# MCU.net
KiCad netlist of a schematic drawn in Altium Designer
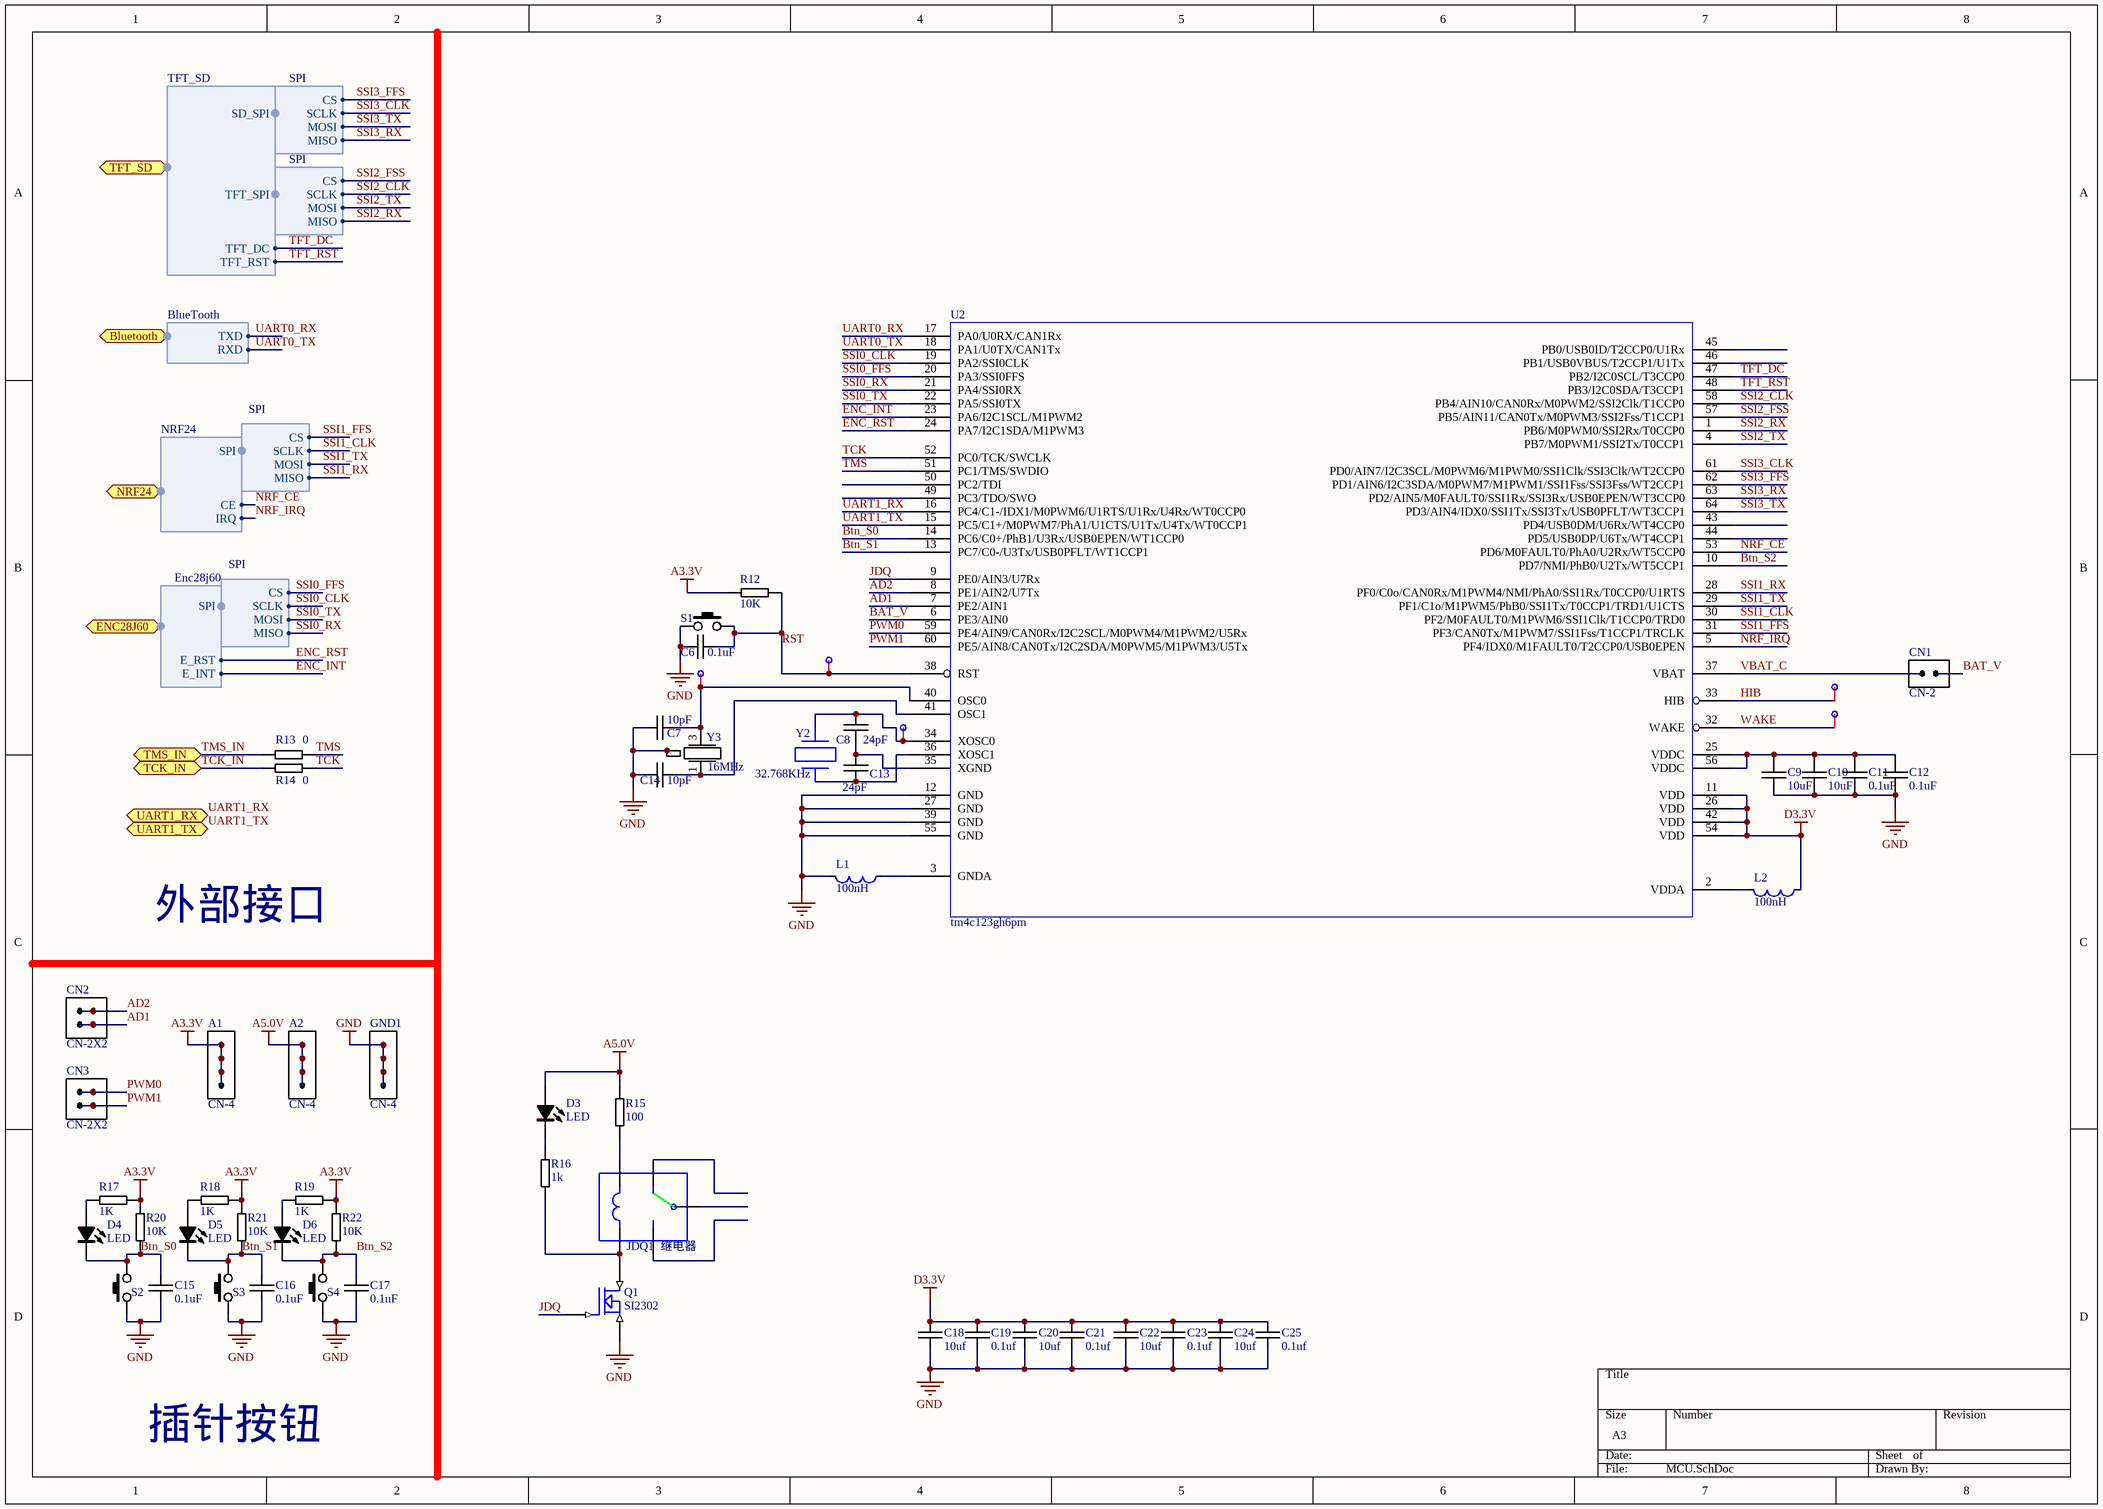
[diagram p0: MCU.SchDoc]

(export (version "E")
  (design (tool "Eeschema 10.0.6"))
  (components
    (comp (ref "A1") (value "CN-4") (footprint "SIP-4") (libsource (lib "开关·连接器") (part "CN-4")))
    (comp (ref "A2") (value "CN-4") (footprint "SIP-4") (libsource (lib "开关·连接器") (part "CN-4")))
    (comp (ref "C6")
      (value "0.1uF")
      (footprint "0805-C")
      (description "贴片")
      (libsource (lib "authuir") (part "CAP_Chip"))
    )
    (comp (ref "C7")
      (value "10pF")
      (footprint "0805-C")
      (description "贴片")
      (libsource (lib "authuir") (part "CAP_Chip"))
    )
    (comp (ref "C8")
      (value "24pF")
      (footprint "0805-C")
      (description "贴片")
      (libsource (lib "authuir") (part "CAP_Chip"))
    )
    (comp (ref "C9")
      (value "10uF")
      (footprint "0805-C")
      (description "贴片")
      (libsource (lib "") (part "CAP_Chip_1"))
    )
    (comp (ref "C10")
      (value "10uF")
      (footprint "0805-C")
      (description "贴片")
      (libsource (lib "") (part "CAP_Chip_1"))
    )
    (comp (ref "C11")
      (value "0.1uF")
      (footprint "0805-C")
      (description "贴片")
      (libsource (lib "") (part "CAP_Chip_1"))
    )
    (comp (ref "C12")
      (value "0.1uF")
      (footprint "0805-C")
      (description "贴片")
      (libsource (lib "") (part "CAP_Chip_1"))
    )
    (comp (ref "C13")
      (value "24pF")
      (footprint "0805-C")
      (description "贴片")
      (libsource (lib "authuir") (part "CAP_Chip"))
    )
    (comp (ref "C14")
      (value "10pF")
      (footprint "0805-C")
      (description "贴片")
      (libsource (lib "authuir") (part "CAP_Chip"))
    )
    (comp (ref "C15")
      (value "0.1uF")
      (footprint "0805-C")
      (description "贴片")
      (libsource (lib "authuir") (part "CAP_Chip"))
    )
    (comp (ref "C16")
      (value "0.1uF")
      (footprint "0805-C")
      (description "贴片")
      (libsource (lib "authuir") (part "CAP_Chip"))
    )
    (comp (ref "C17")
      (value "0.1uF")
      (footprint "0805-C")
      (description "贴片")
      (libsource (lib "authuir") (part "CAP_Chip"))
    )
    (comp (ref "C18")
      (value "10uf")
      (footprint "0603")
      (description "贴片")
      (libsource (lib "authuir") (part "CAP_Chip"))
    )
    (comp (ref "C19")
      (value "0.1uf")
      (footprint "0603")
      (description "贴片")
      (libsource (lib "authuir") (part "CAP_Chip"))
    )
    (comp (ref "C20")
      (value "10uf")
      (footprint "0603")
      (description "贴片")
      (libsource (lib "authuir") (part "CAP_Chip"))
    )
    (comp (ref "C21")
      (value "0.1uf")
      (footprint "0603")
      (description "贴片")
      (libsource (lib "authuir") (part "CAP_Chip"))
    )
    (comp (ref "C22")
      (value "10uf")
      (footprint "0603")
      (description "贴片")
      (libsource (lib "authuir") (part "CAP_Chip"))
    )
    (comp (ref "C23")
      (value "0.1uf")
      (footprint "0603")
      (description "贴片")
      (libsource (lib "authuir") (part "CAP_Chip"))
    )
    (comp (ref "C24")
      (value "10uf")
      (footprint "0603")
      (description "贴片")
      (libsource (lib "authuir") (part "CAP_Chip"))
    )
    (comp (ref "C25")
      (value "0.1uf")
      (footprint "0603")
      (description "贴片")
      (libsource (lib "authuir") (part "CAP_Chip"))
    )
    (comp (ref "CN1") (value "CN-2") (footprint "SIP-2") (libsource (lib "开关·连接器") (part "CN-2")))
    (comp (ref "CN2") (value "CN-2X2") (footprint "IDC-4") (libsource (lib "开关·连接器") (part "CN-2X2")))
    (comp (ref "CN3") (value "CN-2X2") (footprint "IDC-4") (libsource (lib "开关·连接器") (part "CN-2X2")))
    (comp (ref "D3")
      (value "LED")
      (footprint "0805-LED")
      (description "贴片")
      (libsource (lib "authuir") (part "LED"))
    )
    (comp (ref "D4")
      (value "LED")
      (footprint "0805-LED")
      (description "贴片")
      (libsource (lib "authuir") (part "LED"))
    )
    (comp (ref "D5")
      (value "LED")
      (footprint "0805-LED")
      (description "贴片")
      (libsource (lib "authuir") (part "LED"))
    )
    (comp (ref "D6")
      (value "LED")
      (footprint "0805-LED")
      (description "贴片")
      (libsource (lib "authuir") (part "LED"))
    )
    (comp (ref "GND1") (value "CN-4") (footprint "SIP-4") (libsource (lib "开关·连接器") (part "CN-4")))
    (comp (ref "JDQ1") (value "继电器") (footprint "继电器") (libsource (lib "authuir") (part "继电器")))
    (comp (ref "L1") (value "100nH") (footprint "0805") (libsource (lib "authuir") (part "L")))
    (comp (ref "L2") (value "100nH") (footprint "0805") (libsource (lib "authuir") (part "L")))
    (comp (ref "P2") (value "Point") (footprint "Point") (libsource (lib "SIT_开关继电器") (part "Point")))
    (comp (ref "P3") (value "Point") (footprint "Point") (libsource (lib "SIT_开关继电器") (part "Point")))
    (comp (ref "P4") (value "Point") (footprint "Point") (libsource (lib "SIT_开关继电器") (part "Point")))
    (comp (ref "P5") (value "Point") (footprint "Point") (libsource (lib "SIT_开关继电器") (part "Point")))
    (comp (ref "P6") (value "Point") (footprint "Point") (libsource (lib "SIT_开关继电器") (part "Point")))
    (comp (ref "Q1") (value "SI2302") (footprint "sot-23") (libsource (lib "authuir") (part "SI2302")))
    (comp (ref "R12")
      (value "10K")
      (footprint "0805-R")
      (description "贴片")
      (libsource (lib "authuir") (part "RES_Chip"))
    )
    (comp (ref "R13")
      (value "0")
      (footprint "0603")
      (description "贴片")
      (libsource (lib "authuir") (part "RES_Chip"))
    )
    (comp (ref "R14")
      (value "0")
      (footprint "0603")
      (description "贴片")
      (libsource (lib "authuir") (part "RES_Chip"))
    )
    (comp (ref "R15")
      (value "100")
      (footprint "0603")
      (description "贴片")
      (libsource (lib "authuir") (part "RES_Chip"))
    )
    (comp (ref "R16")
      (value "1k")
      (footprint "0805-R")
      (description "贴片")
      (libsource (lib "authuir") (part "RES_Chip"))
    )
    (comp (ref "R17")
      (value "1K")
      (footprint "0805-R")
      (description "贴片")
      (libsource (lib "authuir") (part "RES_Chip"))
    )
    (comp (ref "R18")
      (value "1K")
      (footprint "0805-R")
      (description "贴片")
      (libsource (lib "authuir") (part "RES_Chip"))
    )
    (comp (ref "R19")
      (value "1K")
      (footprint "0805-R")
      (description "贴片")
      (libsource (lib "authuir") (part "RES_Chip"))
    )
    (comp (ref "R20")
      (value "10K")
      (footprint "0805-R")
      (description "贴片")
      (libsource (lib "authuir") (part "RES_Chip"))
    )
    (comp (ref "R21")
      (value "10K")
      (footprint "0805-R")
      (description "贴片")
      (libsource (lib "authuir") (part "RES_Chip"))
    )
    (comp (ref "R22")
      (value "10K")
      (footprint "0805-R")
      (description "贴片")
      (libsource (lib "authuir") (part "RES_Chip"))
    )
    (comp (ref "S1")
      (value "KEY(轻触,6×6×4.3)")
      (footprint "轻触开关(3*6*2.5)")
      (description "1.09.02.0001")
      (libsource (lib "authuir") (part "KEY(轻触,6×6×4.3)"))
    )
    (comp (ref "S2")
      (value "KEY(轻触,6×6×4.3)")
      (footprint "轻触开关(3*6*2.5)")
      (description "1.09.02.0001")
      (libsource (lib "authuir") (part "KEY(轻触,6×6×4.3)"))
    )
    (comp (ref "S3")
      (value "KEY(轻触,6×6×4.3)")
      (footprint "轻触开关(3*6*2.5)")
      (description "1.09.02.0001")
      (libsource (lib "authuir") (part "KEY(轻触,6×6×4.3)"))
    )
    (comp (ref "S4")
      (value "KEY(轻触,6×6×4.3)")
      (footprint "轻触开关(3*6*2.5)")
      (description "1.09.02.0001")
      (libsource (lib "authuir") (part "KEY(轻触,6×6×4.3)"))
    )
    (comp (ref "U2")
      (value "tm4c123gh6pm")
      (footprint "LQFP64")
      (libsource (lib "authuir") (part "tm4c123gh6pm"))
    )
    (comp (ref "Y2")
      (value "32.768KHz")
      (footprint "XTAL(Φ2×6)")
      (libsource (lib "authuir") (part "XTAL_32_768"))
    )
    (comp (ref "Y3") (value "16MHz") (footprint "4脚晶振") (libsource (lib "authuir") (part "XTAL_16M")))
  )
  (nets
    (net (code "5") (name "/AD1") (class "Default")
      (node (ref "CN2") (pin "3") (pinfunction "3_3") (pintype "passive"))
      (node (ref "CN2") (pin "4") (pinfunction "4_4") (pintype "passive"))
      (node (ref "U2") (pin "7") (pinfunction "PE2/AIN1_7") (pintype "passive"))
    )
    (net (code "6") (name "/AD2") (class "Default")
      (node (ref "CN2") (pin "1") (pinfunction "1_1") (pintype "passive"))
      (node (ref "CN2") (pin "2") (pinfunction "2_2") (pintype "passive"))
      (node (ref "U2") (pin "8") (pinfunction "PE1/AIN2/U7Tx_8") (pintype "passive"))
    )
    (net (code "7") (name "/BAT_V") (class "Default")
      (node (ref "CN1") (pin "2") (pinfunction "2_2") (pintype "passive"))
      (node (ref "U2") (pin "6") (pinfunction "PE3/AIN0_6") (pintype "passive"))
    )
    (net (code "8") (name "/Btn_S0") (class "Default")
      (node (ref "C15") (pin "2") (pinfunction "2_2") (pintype "passive"))
      (node (ref "D4") (pin "2") (pinfunction "K_2") (pintype "passive"))
      (node (ref "R20") (pin "2") (pinfunction "2_2") (pintype "passive"))
      (node (ref "S2") (pin "2") (pinfunction "2_2") (pintype "passive"))
      (node (ref "U2") (pin "14") (pinfunction "PC6/C0+/PhB1/U3Rx/USB0EPEN/WT1CCP0_14") (pintype "passive"))
    )
    (net (code "9") (name "/Btn_S1") (class "Default")
      (node (ref "C16") (pin "2") (pinfunction "2_2") (pintype "passive"))
      (node (ref "D5") (pin "2") (pinfunction "K_2") (pintype "passive"))
      (node (ref "R21") (pin "2") (pinfunction "2_2") (pintype "passive"))
      (node (ref "S3") (pin "2") (pinfunction "2_2") (pintype "passive"))
      (node (ref "U2") (pin "13") (pinfunction "PC7/C0-/U3Tx/USB0PFLT/WT1CCP1_13") (pintype "passive"))
    )
    (net (code "10") (name "/Btn_S2") (class "Default")
      (node (ref "C17") (pin "2") (pinfunction "2_2") (pintype "passive"))
      (node (ref "D6") (pin "2") (pinfunction "K_2") (pintype "passive"))
      (node (ref "R22") (pin "2") (pinfunction "2_2") (pintype "passive"))
      (node (ref "S4") (pin "2") (pinfunction "2_2") (pintype "passive"))
      (node (ref "U2") (pin "10") (pinfunction "PD7/NMI/PhB0/U2Tx/WT5CCP1_10") (pintype "passive"))
    )
    (net (code "11") (name "/ENC_INT") (class "Default")
      (node (ref "U2") (pin "23") (pinfunction "PA6/I2C1SCL/M1PWM2_23") (pintype "passive"))
    )
    (net (code "12") (name "/ENC_RST") (class "Default")
      (node (ref "U2") (pin "24") (pinfunction "PA7/I2C1SDA/M1PWM3_24") (pintype "passive"))
    )
    (net (code "13") (name "/HIB") (class "Default")
      (node (ref "P4") (pin "1") (pinfunction "Point_1") (pintype "passive"))
      (node (ref "U2") (pin "33") (pinfunction "HIB_33") (pintype "passive"))
    )
    (net (code "14") (name "/JDQ") (class "Default")
      (node (ref "Q1") (pin "1") (pinfunction "G_1") (pintype "input"))
      (node (ref "U2") (pin "9") (pinfunction "PE0/AIN3/U7Rx_9") (pintype "passive"))
    )
    (net (code "15") (name "/NRF_CE") (class "Default")
      (node (ref "U2") (pin "53") (pinfunction "PD6/M0FAULT0/PhA0/U2Rx/WT5CCP0_53") (pintype "passive"))
    )
    (net (code "16") (name "/NRF_IRQ") (class "Default")
      (node (ref "U2") (pin "5") (pinfunction "PF4/IDX0/M1FAULT0/T2CCP0/USB0EPEN_5") (pintype "passive"))
    )
    (net (code "17") (name "/PWM0") (class "Default")
      (node (ref "CN3") (pin "1") (pinfunction "1_1") (pintype "passive"))
      (node (ref "CN3") (pin "2") (pinfunction "2_2") (pintype "passive"))
      (node (ref "U2") (pin "59") (pinfunction "PE4/AIN9/CAN0Rx/I2C2SCL/M0PWM4/M1PWM2/U5Rx_59") (pintype "passive"))
    )
    (net (code "18") (name "/PWM1") (class "Default")
      (node (ref "CN3") (pin "3") (pinfunction "3_3") (pintype "passive"))
      (node (ref "CN3") (pin "4") (pinfunction "4_4") (pintype "passive"))
      (node (ref "U2") (pin "60") (pinfunction "PE5/AIN8/CAN0Tx/I2C2SDA/M0PWM5/M1PWM3/U5Tx_60") (pintype "passive"))
    )
    (net (code "19") (name "/RST") (class "Default")
      (node (ref "C6") (pin "2") (pinfunction "2_2") (pintype "passive"))
      (node (ref "P2") (pin "1") (pinfunction "Point_1") (pintype "passive"))
      (node (ref "R12") (pin "1") (pinfunction "1_1") (pintype "passive"))
      (node (ref "S1") (pin "2") (pinfunction "2_2") (pintype "passive"))
      (node (ref "U2") (pin "38") (pinfunction "RST_38") (pintype "passive"))
    )
    (net (code "20") (name "/SSI0_CLK") (class "Default")
      (node (ref "U2") (pin "19") (pinfunction "PA2/SSI0CLK_19") (pintype "passive"))
    )
    (net (code "21") (name "/SSI0_FFS") (class "Default")
      (node (ref "U2") (pin "20") (pinfunction "PA3/SSI0FFS_20") (pintype "passive"))
    )
    (net (code "22") (name "/SSI0_RX") (class "Default")
      (node (ref "U2") (pin "21") (pinfunction "PA4/SSI0RX_21") (pintype "passive"))
    )
    (net (code "23") (name "/SSI0_TX") (class "Default")
      (node (ref "U2") (pin "22") (pinfunction "PA5/SSI0TX_22") (pintype "passive"))
    )
    (net (code "24") (name "/SSI1_CLK") (class "Default")
      (node (ref "U2") (pin "30") (pinfunction "PF2/M0FAULT0/M1PWM6/SSI1Clk/T1CCP0/TRD0_30") (pintype "passive"))
    )
    (net (code "25") (name "/SSI1_FFS") (class "Default")
      (node (ref "U2") (pin "31") (pinfunction "PF3/CAN0Tx/M1PWM7/SSI1Fss/T1CCP1/TRCLK_31") (pintype "passive"))
    )
    (net (code "26") (name "/SSI1_RX") (class "Default")
      (node (ref "U2") (pin "28") (pinfunction "PF0/C0o/CAN0Rx/M1PWM4/NMI/PhA0/SSI1Rx/T0CCP0/U1RTS_28") (pintype "passive"))
    )
    (net (code "27") (name "/SSI1_TX") (class "Default")
      (node (ref "U2") (pin "29") (pinfunction "PF1/C1o/M1PWM5/PhB0/SSI1Tx/T0CCP1/TRD1/U1CTS_29") (pintype "passive"))
    )
    (net (code "28") (name "/SSI2_CLK") (class "Default")
      (node (ref "U2") (pin "58") (pinfunction "PB4/AIN10/CAN0Rx/M0PWM2/SSI2Clk/T1CCP0_58") (pintype "passive"))
    )
    (net (code "29") (name "/SSI2_FSS") (class "Default")
      (node (ref "U2") (pin "57") (pinfunction "PB5/AIN11/CAN0Tx/M0PWM3/SSI2Fss/T1CCP1_57") (pintype "passive"))
    )
    (net (code "30") (name "/SSI2_RX") (class "Default")
      (node (ref "U2") (pin "1") (pinfunction "PB6/M0PWM0/SSI2Rx/T0CCP0_1") (pintype "passive"))
    )
    (net (code "31") (name "/SSI2_TX") (class "Default")
      (node (ref "U2") (pin "4") (pinfunction "PB7/M0PWM1/SSI2Tx/T0CCP1_4") (pintype "passive"))
    )
    (net (code "32") (name "/SSI3_CLK") (class "Default")
      (node (ref "U2") (pin "61") (pinfunction "PD0/AIN7/I2C3SCL/M0PWM6/M1PWM0/SSI1Clk/SSI3Clk/WT2CCP0_61") (pintype "passive"))
    )
    (net (code "33") (name "/SSI3_FFS") (class "Default")
      (node (ref "U2") (pin "62") (pinfunction "PD1/AIN6/I2C3SDA/M0PWM7/M1PWM1/SSI1Fss/SSI3Fss/WT2CCP1_62") (pintype "passive"))
    )
    (net (code "34") (name "/SSI3_RX") (class "Default")
      (node (ref "U2") (pin "63") (pinfunction "PD2/AIN5/M0FAULT0/SSI1Rx/SSI3Rx/USB0EPEN/WT3CCP0_63") (pintype "passive"))
    )
    (net (code "35") (name "/SSI3_TX") (class "Default")
      (node (ref "U2") (pin "64") (pinfunction "PD3/AIN4/IDX0/SSI1Tx/SSI3Tx/USB0PFLT/WT3CCP1_64") (pintype "passive"))
    )
    (net (code "36") (name "/TCK") (class "Default")
      (node (ref "R14") (pin "2") (pinfunction "2_2") (pintype "passive"))
      (node (ref "U2") (pin "52") (pinfunction "PC0/TCK/SWCLK_52") (pintype "passive"))
    )
    (net (code "37") (name "/TCK_IN") (class "Default")
      (node (ref "R14") (pin "1") (pinfunction "1_1") (pintype "passive"))
    )
    (net (code "38") (name "/TFT_DC") (class "Default")
      (node (ref "U2") (pin "47") (pinfunction "PB2/I2C0SCL/T3CCP0_47") (pintype "passive"))
    )
    (net (code "39") (name "/TFT_RST") (class "Default")
      (node (ref "U2") (pin "48") (pinfunction "PB3/I2C0SDA/T3CCP1_48") (pintype "passive"))
    )
    (net (code "40") (name "/TMS") (class "Default")
      (node (ref "R13") (pin "2") (pinfunction "2_2") (pintype "passive"))
      (node (ref "U2") (pin "51") (pinfunction "PC1/TMS/SWDIO_51") (pintype "passive"))
    )
    (net (code "41") (name "/TMS_IN") (class "Default")
      (node (ref "R13") (pin "1") (pinfunction "1_1") (pintype "passive"))
    )
    (net (code "42") (name "/UART0_RX") (class "Default")
      (node (ref "U2") (pin "17") (pinfunction "PA0/U0RX/CAN1Rx_17") (pintype "passive"))
    )
    (net (code "43") (name "/UART0_TX") (class "Default")
      (node (ref "U2") (pin "18") (pinfunction "PA1/U0TX/CAN1Tx_18") (pintype "passive"))
    )
    (net (code "44") (name "/UART1_RX") (class "Default")
      (node (ref "U2") (pin "16") (pinfunction "PC4/C1-/IDX1/M0PWM6/U1RTS/U1Rx/U4Rx/WT0CCP0_16") (pintype "passive"))
    )
    (net (code "45") (name "/UART1_TX") (class "Default")
      (node (ref "U2") (pin "15") (pinfunction "PC5/C1+/M0PWM7/PhA1/U1CTS/U1Tx/U4Tx/WT0CCP1_15") (pintype "passive"))
    )
    (net (code "46") (name "/VBAT_C") (class "Default")
      (node (ref "CN1") (pin "1") (pinfunction "1_1") (pintype "passive"))
      (node (ref "U2") (pin "37") (pinfunction "VBAT_37") (pintype "passive"))
    )
    (net (code "47") (name "/WAKE") (class "Default")
      (node (ref "P5") (pin "1") (pinfunction "Point_1") (pintype "passive"))
      (node (ref "U2") (pin "32") (pinfunction "WAKE_32") (pintype "passive"))
    )
    (net (code "52") (name "A3.3V") (class "Default")
      (node (ref "A1") (pin "1") (pinfunction "1_1") (pintype "passive"))
      (node (ref "A1") (pin "2") (pinfunction "2_2") (pintype "passive"))
      (node (ref "A1") (pin "3") (pinfunction "3_3") (pintype "passive"))
      (node (ref "A1") (pin "4") (pinfunction "4_4") (pintype "passive"))
      (node (ref "R12") (pin "2") (pinfunction "2_2") (pintype "passive"))
      (node (ref "R17") (pin "2") (pinfunction "2_2") (pintype "passive"))
      (node (ref "R18") (pin "2") (pinfunction "2_2") (pintype "passive"))
      (node (ref "R19") (pin "2") (pinfunction "2_2") (pintype "passive"))
      (node (ref "R20") (pin "1") (pinfunction "1_1") (pintype "passive"))
      (node (ref "R21") (pin "1") (pinfunction "1_1") (pintype "passive"))
      (node (ref "R22") (pin "1") (pinfunction "1_1") (pintype "passive"))
    )
    (net (code "53") (name "A5.0V") (class "Default")
      (node (ref "A2") (pin "1") (pinfunction "1_1") (pintype "passive"))
      (node (ref "A2") (pin "2") (pinfunction "2_2") (pintype "passive"))
      (node (ref "A2") (pin "3") (pinfunction "3_3") (pintype "passive"))
      (node (ref "A2") (pin "4") (pinfunction "4_4") (pintype "passive"))
      (node (ref "D3") (pin "1") (pinfunction "A_1") (pintype "passive"))
      (node (ref "R15") (pin "1") (pinfunction "1_1") (pintype "passive"))
    )
    (net (code "54") (name "D3.3V") (class "Default")
      (node (ref "C18") (pin "1") (pinfunction "1_1") (pintype "passive"))
      (node (ref "C19") (pin "1") (pinfunction "1_1") (pintype "passive"))
      (node (ref "C20") (pin "1") (pinfunction "1_1") (pintype "passive"))
      (node (ref "C21") (pin "1") (pinfunction "1_1") (pintype "passive"))
      (node (ref "C22") (pin "1") (pinfunction "1_1") (pintype "passive"))
      (node (ref "C23") (pin "1") (pinfunction "1_1") (pintype "passive"))
      (node (ref "C24") (pin "1") (pinfunction "1_1") (pintype "passive"))
      (node (ref "C25") (pin "1") (pinfunction "1_1") (pintype "passive"))
      (node (ref "L2") (pin "2") (pinfunction "2_2") (pintype "passive"))
      (node (ref "U2") (pin "11") (pinfunction "VDD_11") (pintype "passive"))
      (node (ref "U2") (pin "26") (pinfunction "VDD_26") (pintype "passive"))
      (node (ref "U2") (pin "42") (pinfunction "VDD_42") (pintype "passive"))
      (node (ref "U2") (pin "54") (pinfunction "VDD_54") (pintype "passive"))
    )
    (net (code "55") (name "GND") (class "Default")
      (node (ref "C10") (pin "2") (pinfunction "2_2") (pintype "passive"))
      (node (ref "C11") (pin "2") (pinfunction "2_2") (pintype "passive"))
      (node (ref "C12") (pin "2") (pinfunction "2_2") (pintype "passive"))
      (node (ref "C14") (pin "1") (pinfunction "1_1") (pintype "passive"))
      (node (ref "C15") (pin "1") (pinfunction "1_1") (pintype "passive"))
      (node (ref "C16") (pin "1") (pinfunction "1_1") (pintype "passive"))
      (node (ref "C17") (pin "1") (pinfunction "1_1") (pintype "passive"))
      (node (ref "C18") (pin "2") (pinfunction "2_2") (pintype "passive"))
      (node (ref "C19") (pin "2") (pinfunction "2_2") (pintype "passive"))
      (node (ref "C20") (pin "2") (pinfunction "2_2") (pintype "passive"))
      (node (ref "C21") (pin "2") (pinfunction "2_2") (pintype "passive"))
      (node (ref "C22") (pin "2") (pinfunction "2_2") (pintype "passive"))
      (node (ref "C23") (pin "2") (pinfunction "2_2") (pintype "passive"))
      (node (ref "C24") (pin "2") (pinfunction "2_2") (pintype "passive"))
      (node (ref "C25") (pin "2") (pinfunction "2_2") (pintype "passive"))
      (node (ref "C6") (pin "1") (pinfunction "1_1") (pintype "passive"))
      (node (ref "C7") (pin "1") (pinfunction "1_1") (pintype "passive"))
      (node (ref "C9") (pin "2") (pinfunction "2_2") (pintype "passive"))
      (node (ref "GND1") (pin "1") (pinfunction "1_1") (pintype "passive"))
      (node (ref "GND1") (pin "2") (pinfunction "2_2") (pintype "passive"))
      (node (ref "GND1") (pin "3") (pinfunction "3_3") (pintype "passive"))
      (node (ref "GND1") (pin "4") (pinfunction "4_4") (pintype "passive"))
      (node (ref "L1") (pin "1") (pinfunction "1_1") (pintype "passive"))
      (node (ref "Q1") (pin "2") (pinfunction "S_2") (pintype "input"))
      (node (ref "S1") (pin "1") (pinfunction "1_1") (pintype "passive"))
      (node (ref "S2") (pin "1") (pinfunction "1_1") (pintype "passive"))
      (node (ref "S3") (pin "1") (pinfunction "1_1") (pintype "passive"))
      (node (ref "S4") (pin "1") (pinfunction "1_1") (pintype "passive"))
      (node (ref "U2") (pin "12") (pinfunction "GND_12") (pintype "passive"))
      (node (ref "U2") (pin "27") (pinfunction "GND_27") (pintype "passive"))
      (node (ref "U2") (pin "39") (pinfunction "GND_39") (pintype "passive"))
      (node (ref "U2") (pin "55") (pinfunction "GND_55") (pintype "passive"))
      (node (ref "Y3") (pin "2") (pinfunction "G_2") (pintype "passive"))
      (node (ref "Y3") (pin "4") (pinfunction "G_4") (pintype "passive"))
    )
    (net (code "56") (name "Net-(C10-Pad1)") (class "Default")
      (node (ref "C10") (pin "1") (pinfunction "1_1") (pintype "passive"))
      (node (ref "C11") (pin "1") (pinfunction "1_1") (pintype "passive"))
      (node (ref "C12") (pin "1") (pinfunction "1_1") (pintype "passive"))
      (node (ref "C9") (pin "1") (pinfunction "1_1") (pintype "passive"))
      (node (ref "U2") (pin "25") (pinfunction "VDDC_25") (pintype "passive"))
      (node (ref "U2") (pin "56") (pinfunction "VDDC_56") (pintype "passive"))
    )
    (net (code "57") (name "Net-(D3-K)") (class "Default")
      (node (ref "D3") (pin "2") (pinfunction "K_2") (pintype "passive"))
      (node (ref "R16") (pin "1") (pinfunction "1_1") (pintype "passive"))
    )
    (net (code "58") (name "Net-(D4-A)") (class "Default")
      (node (ref "D4") (pin "1") (pinfunction "A_1") (pintype "passive"))
      (node (ref "R17") (pin "1") (pinfunction "1_1") (pintype "passive"))
    )
    (net (code "59") (name "Net-(D5-A)") (class "Default")
      (node (ref "D5") (pin "1") (pinfunction "A_1") (pintype "passive"))
      (node (ref "R18") (pin "1") (pinfunction "1_1") (pintype "passive"))
    )
    (net (code "60") (name "Net-(D6-A)") (class "Default")
      (node (ref "D6") (pin "1") (pinfunction "A_1") (pintype "passive"))
      (node (ref "R19") (pin "1") (pinfunction "1_1") (pintype "passive"))
    )
    (net (code "61") (name "Net-(JDQ1-I1)") (class "Default")
      (node (ref "JDQ1") (pin "2") (pinfunction "I1_2") (pintype "passive"))
      (node (ref "R15") (pin "2") (pinfunction "2_2") (pintype "passive"))
    )
    (net (code "62") (name "Net-(JDQ1-I2)") (class "Default")
      (node (ref "JDQ1") (pin "5") (pinfunction "I2_5") (pintype "passive"))
      (node (ref "Q1") (pin "3") (pinfunction "D_3") (pintype "input"))
      (node (ref "R16") (pin "2") (pinfunction "2_2") (pintype "passive"))
    )
    (net (code "63") (name "Net-(P3-Point)") (class "Default")
      (node (ref "C7") (pin "2") (pinfunction "2_2") (pintype "passive"))
      (node (ref "P3") (pin "1") (pinfunction "Point_1") (pintype "passive"))
      (node (ref "U2") (pin "40") (pinfunction "OSC0_40") (pintype "passive"))
      (node (ref "Y3") (pin "3") (pinfunction "O_3") (pintype "passive"))
    )
    (net (code "64") (name "Net-(P6-Point)") (class "Default")
      (node (ref "C8") (pin "1") (pinfunction "1_1") (pintype "passive"))
      (node (ref "P6") (pin "1") (pinfunction "Point_1") (pintype "passive"))
      (node (ref "U2") (pin "34") (pinfunction "XOSC0_34") (pintype "passive"))
      (node (ref "Y2") (pin "1") (pinfunction "1_1") (pintype "passive"))
    )
    (net (code "65") (name "Net-(U2-GNDA)") (class "Default")
      (node (ref "L1") (pin "2") (pinfunction "2_2") (pintype "passive"))
      (node (ref "U2") (pin "3") (pinfunction "GNDA_3") (pintype "passive"))
    )
    (net (code "66") (name "Net-(U2-OSC1)") (class "Default")
      (node (ref "C14") (pin "2") (pinfunction "2_2") (pintype "passive"))
      (node (ref "U2") (pin "41") (pinfunction "OSC1_41") (pintype "passive"))
      (node (ref "Y3") (pin "1") (pinfunction "O_1") (pintype "passive"))
    )
    (net (code "67") (name "Net-(U2-VDDA)") (class "Default")
      (node (ref "L2") (pin "1") (pinfunction "1_1") (pintype "passive"))
      (node (ref "U2") (pin "2") (pinfunction "VDDA_2") (pintype "passive"))
    )
    (net (code "68") (name "Net-(U2-XGND)") (class "Default")
      (node (ref "C13") (pin "1") (pinfunction "1_1") (pintype "passive"))
      (node (ref "C8") (pin "2") (pinfunction "2_2") (pintype "passive"))
      (node (ref "U2") (pin "35") (pinfunction "XGND_35") (pintype "passive"))
    )
    (net (code "69") (name "Net-(U2-XOSC1)") (class "Default")
      (node (ref "C13") (pin "2") (pinfunction "2_2") (pintype "passive"))
      (node (ref "U2") (pin "36") (pinfunction "XOSC1_36") (pintype "passive"))
      (node (ref "Y2") (pin "2") (pinfunction "2_2") (pintype "passive"))
    )
    (net (code "70") (name "unconnected-(JDQ1-5-Pad3)") (class "Default")
      (node (ref "JDQ1") (pin "3") (pinfunction "5_3") (pintype "passive"))
    )
    (net (code "71") (name "unconnected-(JDQ1-Pad1)") (class "Default")
      (node (ref "JDQ1") (pin "1") (pinfunction "1_1") (pintype "passive"))
    )
    (net (code "72") (name "unconnected-(JDQ1-Pad4)") (class "Default")
      (node (ref "JDQ1") (pin "4") (pinfunction "4_4") (pintype "passive"))
    )
    (net (code "73") (name "unconnected-(U2-PB0{slash}USB0ID{slash}T2CCP0{slash}U1Rx-Pad45)") (class "Default")
      (node (ref "U2") (pin "45") (pinfunction "PB0/USB0ID/T2CCP0/U1Rx_45") (pintype "passive"))
    )
    (net (code "74") (name "unconnected-(U2-PB1{slash}USB0VBUS{slash}T2CCP1{slash}U1Tx-Pad46)") (class "Default")
      (node (ref "U2") (pin "46") (pinfunction "PB1/USB0VBUS/T2CCP1/U1Tx_46") (pintype "passive"))
    )
    (net (code "75") (name "unconnected-(U2-PC2{slash}TDI-Pad50)") (class "Default")
      (node (ref "U2") (pin "50") (pinfunction "PC2/TDI_50") (pintype "passive"))
    )
    (net (code "76") (name "unconnected-(U2-PC3{slash}TDO{slash}SWO-Pad49)") (class "Default")
      (node (ref "U2") (pin "49") (pinfunction "PC3/TDO/SWO_49") (pintype "passive"))
    )
    (net (code "77") (name "unconnected-(U2-PD4{slash}USB0DM{slash}U6Rx{slash}WT4CCP0-Pad43)") (class "Default")
      (node (ref "U2") (pin "43") (pinfunction "PD4/USB0DM/U6Rx/WT4CCP0_43") (pintype "passive"))
    )
    (net (code "78") (name "unconnected-(U2-PD5{slash}USB0DP{slash}U6Tx{slash}WT4CCP1-Pad44)") (class "Default")
      (node (ref "U2") (pin "44") (pinfunction "PD5/USB0DP/U6Tx/WT4CCP1_44") (pintype "passive"))
    )
  )
)
